# HeadphoneAmplifierUsingLM386.net
KiCad netlist of a schematic drawn in EAGLE
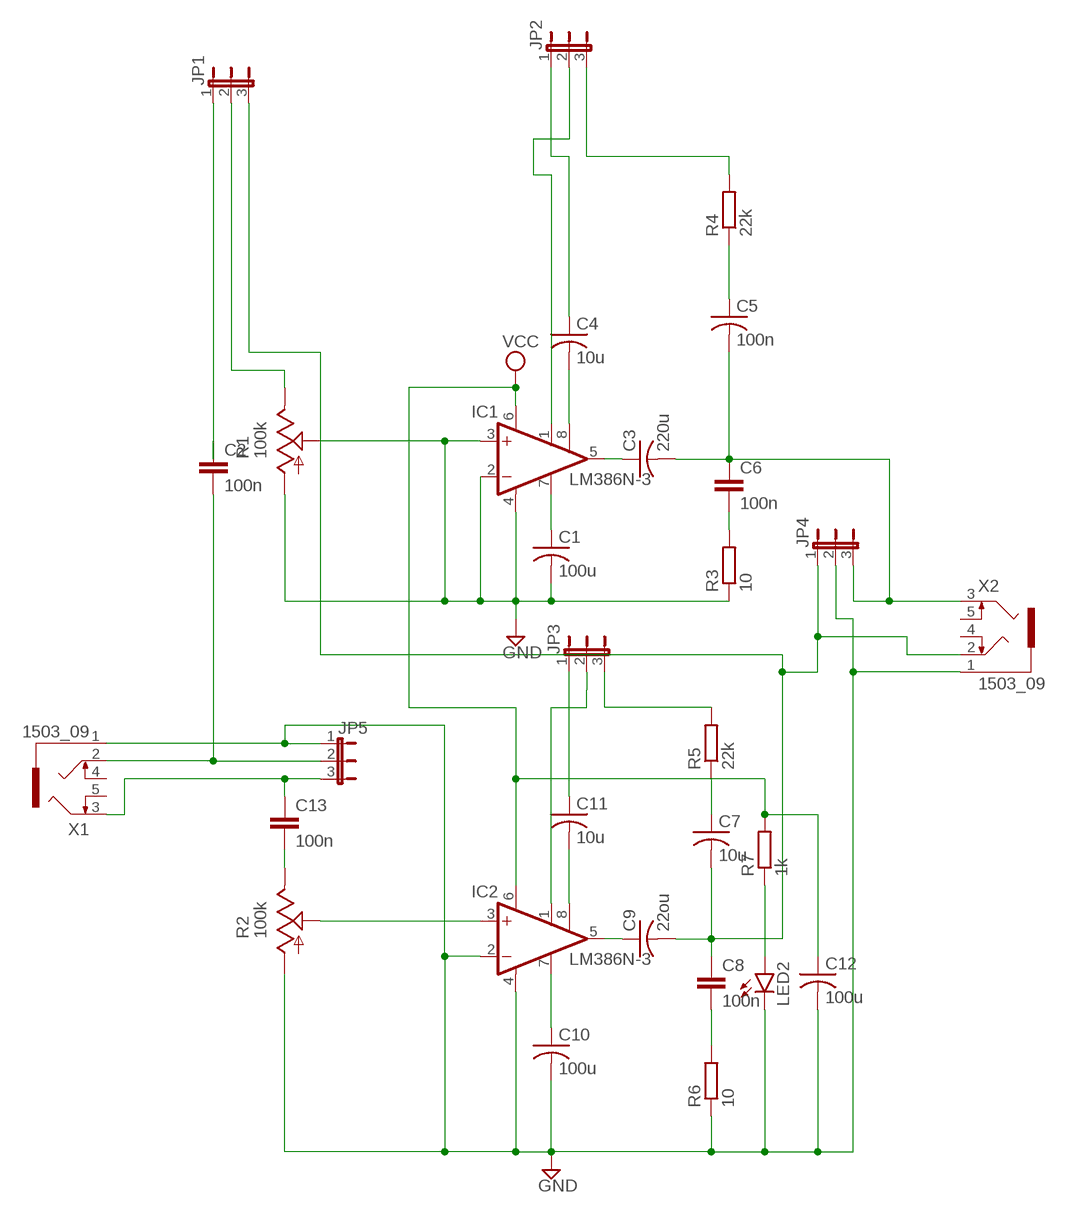
[diagram p0: schematic, sheet 1]

(export (version "E")
  (design (tool "Eeschema 10.0.6"))
  (components
    (comp (ref "C1")
      (value "100u")
      (footprint "eagle-import:C025-030X050")
      (libsource (lib "eagle-import") (part "C-US025-030X050"))
    )
    (comp (ref "C2")
      (value "100n")
      (footprint "eagle-import:C025-030X050")
      (libsource (lib "eagle-import") (part "C-EU025-030X050"))
    )
    (comp (ref "C3")
      (value "220u")
      (footprint "eagle-import:C025-030X050")
      (libsource (lib "eagle-import") (part "C-US025-030X050"))
    )
    (comp (ref "C4")
      (value "10u")
      (footprint "eagle-import:C025-030X050")
      (libsource (lib "eagle-import") (part "C-US025-030X050"))
    )
    (comp (ref "C5")
      (value "100n")
      (footprint "eagle-import:C025-030X050")
      (libsource (lib "eagle-import") (part "C-US025-030X050"))
    )
    (comp (ref "C6")
      (value "100n")
      (footprint "eagle-import:C025-030X050")
      (libsource (lib "eagle-import") (part "C-EU025-030X050"))
    )
    (comp (ref "C7")
      (value "10u")
      (footprint "eagle-import:C025-030X050")
      (libsource (lib "eagle-import") (part "C-US025-030X050"))
    )
    (comp (ref "C8")
      (value "100n")
      (footprint "eagle-import:C025-030X050")
      (libsource (lib "eagle-import") (part "C-EU025-030X050"))
    )
    (comp (ref "C9")
      (value "22ou")
      (footprint "eagle-import:C025-030X050")
      (libsource (lib "eagle-import") (part "C-US025-030X050"))
    )
    (comp (ref "C10")
      (value "100u")
      (footprint "eagle-import:C025-030X050")
      (libsource (lib "eagle-import") (part "C-US025-030X050"))
    )
    (comp (ref "C11")
      (value "10u")
      (footprint "eagle-import:C025-030X050")
      (libsource (lib "eagle-import") (part "C-US025-030X050"))
    )
    (comp (ref "C12")
      (value "100u")
      (footprint "eagle-import:C025-030X050")
      (libsource (lib "eagle-import") (part "C-US025-030X050"))
    )
    (comp (ref "C13")
      (value "100n")
      (footprint "eagle-import:C025-030X050")
      (libsource (lib "eagle-import") (part "C-EU025-030X050"))
    )
    (comp (ref "IC1")
      (value "LM386N-3")
      (footprint "eagle-import:DIL08")
      (libsource (lib "eagle-import") (part "LM386?-N3"))
    )
    (comp (ref "IC2")
      (value "LM386N-3")
      (footprint "eagle-import:DIL08")
      (libsource (lib "eagle-import") (part "LM386?-N3"))
    )
    (comp (ref "JP1")
      (value "JP2E")
      (footprint "eagle-import:JP2")
      (libsource (lib "eagle-import") (part "JP2E"))
    )
    (comp (ref "JP2")
      (value "JP2E")
      (footprint "eagle-import:JP2")
      (libsource (lib "eagle-import") (part "JP2E"))
    )
    (comp (ref "JP3")
      (value "JP2E")
      (footprint "eagle-import:JP2")
      (libsource (lib "eagle-import") (part "JP2E"))
    )
    (comp (ref "JP4")
      (value "JP2E")
      (footprint "eagle-import:JP2")
      (libsource (lib "eagle-import") (part "JP2E"))
    )
    (comp (ref "JP5")
      (value "JP2E")
      (footprint "eagle-import:JP2")
      (libsource (lib "eagle-import") (part "JP2E"))
    )
    (comp (ref "LED2")
      (value "LED3MM")
      (footprint "eagle-import:LED3MM")
      (libsource (lib "eagle-import") (part "LED3MM"))
    )
    (comp (ref "R1")
      (value "100k")
      (footprint "eagle-import:3223W")
      (libsource (lib "eagle-import") (part "TRIM_US-3223W"))
    )
    (comp (ref "R2")
      (value "100k")
      (footprint "eagle-import:3223W")
      (libsource (lib "eagle-import") (part "TRIM_US-3223W"))
    )
    (comp (ref "R3")
      (value "10")
      (footprint "eagle-import:0309_12")
      (libsource (lib "eagle-import") (part "R-EU_0309/12"))
    )
    (comp (ref "R4")
      (value "22k")
      (footprint "eagle-import:0309_12")
      (libsource (lib "eagle-import") (part "R-EU_0309/12"))
    )
    (comp (ref "R5")
      (value "22k")
      (footprint "eagle-import:0309_12")
      (libsource (lib "eagle-import") (part "R-EU_0309/12"))
    )
    (comp (ref "R6")
      (value "10")
      (footprint "eagle-import:0309_12")
      (libsource (lib "eagle-import") (part "R-EU_0309/12"))
    )
    (comp (ref "R7")
      (value "1k")
      (footprint "eagle-import:0309_12")
      (libsource (lib "eagle-import") (part "R-EU_0309/12"))
    )
    (comp (ref "X1")
      (value "1503_09")
      (footprint "eagle-import:1503_09")
      (libsource (lib "eagle-import") (part "1503_09"))
    )
    (comp (ref "X2")
      (value "1503_09")
      (footprint "eagle-import:1503_09")
      (libsource (lib "eagle-import") (part "1503_09"))
    )
  )
  (nets
    (net (code "1") (name "GND") (class "Default")
      (node (ref "C1") (pin "2") (pinfunction "2_2") (pintype "passive"))
      (node (ref "C10") (pin "2") (pinfunction "2_2") (pintype "passive"))
      (node (ref "C12") (pin "2") (pinfunction "2_2") (pintype "passive"))
      (node (ref "IC1") (pin "2") (pinfunction "-IN_2") (pintype "input"))
      (node (ref "IC1") (pin "3") (pinfunction "+IN_3") (pintype "input"))
      (node (ref "IC1") (pin "4") (pinfunction "GND_4") (pintype "power_in"))
      (node (ref "IC2") (pin "2") (pinfunction "-IN_2") (pintype "input"))
      (node (ref "IC2") (pin "4") (pinfunction "GND_4") (pintype "power_in"))
      (node (ref "JP4") (pin "2") (pinfunction "2_2") (pintype "passive"))
      (node (ref "JP5") (pin "1") (pinfunction "1_1") (pintype "passive"))
      (node (ref "LED2") (pin "K") (pinfunction "C_K") (pintype "passive"))
      (node (ref "R1") (pin "1") (pinfunction "A_1") (pintype "passive"))
      (node (ref "R1") (pin "2") (pinfunction "S_2") (pintype "passive"))
      (node (ref "R2") (pin "1") (pinfunction "A_1") (pintype "passive"))
      (node (ref "R3") (pin "1") (pinfunction "1_1") (pintype "passive"))
      (node (ref "R6") (pin "1") (pinfunction "1_1") (pintype "passive"))
      (node (ref "X1") (pin "1") (pinfunction "1_1") (pintype "passive"))
      (node (ref "X2") (pin "1") (pinfunction "1_1") (pintype "passive"))
    )
    (net (code "2") (name "Net-(C2-Pad1)") (class "Default")
      (node (ref "C2") (pin "1") (pinfunction "1_1") (pintype "passive"))
      (node (ref "JP1") (pin "1") (pinfunction "1_1") (pintype "passive"))
    )
    (net (code "3") (name "Net-(C2-Pad2)") (class "Default")
      (node (ref "C2") (pin "2") (pinfunction "2_2") (pintype "passive"))
      (node (ref "JP5") (pin "2") (pinfunction "2_2") (pintype "passive"))
      (node (ref "X1") (pin "2") (pinfunction "2_2") (pintype "passive"))
    )
    (net (code "4") (name "Net-(C3-Pad2)") (class "Default")
      (node (ref "C3") (pin "2") (pinfunction "2_2") (pintype "passive"))
      (node (ref "C5") (pin "2") (pinfunction "2_2") (pintype "passive"))
      (node (ref "C6") (pin "1") (pinfunction "1_1") (pintype "passive"))
      (node (ref "JP4") (pin "3") (pinfunction "3_3") (pintype "passive"))
      (node (ref "X2") (pin "3") (pinfunction "3_3") (pintype "passive"))
    )
    (net (code "5") (name "Net-(C4-Pad1)") (class "Default")
      (node (ref "C4") (pin "1") (pinfunction "1_1") (pintype "passive"))
      (node (ref "JP2") (pin "1") (pinfunction "1_1") (pintype "passive"))
    )
    (net (code "6") (name "Net-(C4-Pad2)") (class "Default")
      (node (ref "C4") (pin "2") (pinfunction "2_2") (pintype "passive"))
      (node (ref "IC1") (pin "8") (pinfunction "GAIN_8") (pintype "passive"))
    )
    (net (code "7") (name "Net-(C5-Pad1)") (class "Default")
      (node (ref "C5") (pin "1") (pinfunction "1_1") (pintype "passive"))
      (node (ref "R4") (pin "1") (pinfunction "1_1") (pintype "passive"))
    )
    (net (code "8") (name "Net-(C6-Pad2)") (class "Default")
      (node (ref "C6") (pin "2") (pinfunction "2_2") (pintype "passive"))
      (node (ref "R3") (pin "2") (pinfunction "2_2") (pintype "passive"))
    )
    (net (code "9") (name "Net-(C7-Pad1)") (class "Default")
      (node (ref "C7") (pin "1") (pinfunction "1_1") (pintype "passive"))
      (node (ref "R5") (pin "1") (pinfunction "1_1") (pintype "passive"))
    )
    (net (code "10") (name "Net-(C7-Pad2)") (class "Default")
      (node (ref "C7") (pin "2") (pinfunction "2_2") (pintype "passive"))
      (node (ref "C8") (pin "1") (pinfunction "1_1") (pintype "passive"))
      (node (ref "C9") (pin "2") (pinfunction "2_2") (pintype "passive"))
      (node (ref "JP1") (pin "3") (pinfunction "3_3") (pintype "passive"))
      (node (ref "JP4") (pin "1") (pinfunction "1_1") (pintype "passive"))
      (node (ref "X2") (pin "2") (pinfunction "2_2") (pintype "passive"))
    )
    (net (code "11") (name "Net-(C8-Pad2)") (class "Default")
      (node (ref "C8") (pin "2") (pinfunction "2_2") (pintype "passive"))
      (node (ref "R6") (pin "2") (pinfunction "2_2") (pintype "passive"))
    )
    (net (code "12") (name "Net-(C11-Pad1)") (class "Default")
      (node (ref "C11") (pin "1") (pinfunction "1_1") (pintype "passive"))
      (node (ref "JP3") (pin "1") (pinfunction "1_1") (pintype "passive"))
    )
    (net (code "13") (name "Net-(C11-Pad2)") (class "Default")
      (node (ref "C11") (pin "2") (pinfunction "2_2") (pintype "passive"))
      (node (ref "IC2") (pin "8") (pinfunction "GAIN_8") (pintype "passive"))
    )
    (net (code "14") (name "Net-(C13-Pad1)") (class "Default")
      (node (ref "C13") (pin "1") (pinfunction "1_1") (pintype "passive"))
      (node (ref "JP5") (pin "3") (pinfunction "3_3") (pintype "passive"))
      (node (ref "X1") (pin "3") (pinfunction "3_3") (pintype "passive"))
    )
    (net (code "15") (name "Net-(IC1-BYPASS)") (class "Default")
      (node (ref "C1") (pin "1") (pinfunction "1_1") (pintype "passive"))
      (node (ref "IC1") (pin "7") (pinfunction "BYPASS_7") (pintype "passive"))
    )
    (net (code "16") (name "Net-(IC1-GAIN-Pad1)") (class "Default")
      (node (ref "IC1") (pin "1") (pinfunction "GAIN_1") (pintype "passive"))
      (node (ref "JP2") (pin "2") (pinfunction "2_2") (pintype "passive"))
    )
    (net (code "17") (name "Net-(IC1-OUT)") (class "Default")
      (node (ref "C3") (pin "1") (pinfunction "1_1") (pintype "passive"))
      (node (ref "IC1") (pin "5") (pinfunction "OUT_5") (pintype "output"))
    )
    (net (code "18") (name "Net-(IC2-+IN)") (class "Default")
      (node (ref "IC2") (pin "3") (pinfunction "+IN_3") (pintype "input"))
      (node (ref "R2") (pin "2") (pinfunction "S_2") (pintype "passive"))
    )
    (net (code "19") (name "Net-(IC2-BYPASS)") (class "Default")
      (node (ref "C10") (pin "1") (pinfunction "1_1") (pintype "passive"))
      (node (ref "IC2") (pin "7") (pinfunction "BYPASS_7") (pintype "passive"))
    )
    (net (code "20") (name "Net-(IC2-GAIN-Pad1)") (class "Default")
      (node (ref "IC2") (pin "1") (pinfunction "GAIN_1") (pintype "passive"))
      (node (ref "JP3") (pin "2") (pinfunction "2_2") (pintype "passive"))
    )
    (net (code "21") (name "Net-(IC2-OUT)") (class "Default")
      (node (ref "C9") (pin "1") (pinfunction "1_1") (pintype "passive"))
      (node (ref "IC2") (pin "5") (pinfunction "OUT_5") (pintype "output"))
    )
    (net (code "22") (name "Net-(JP2-Pad3)") (class "Default")
      (node (ref "JP2") (pin "3") (pinfunction "3_3") (pintype "passive"))
      (node (ref "R4") (pin "2") (pinfunction "2_2") (pintype "passive"))
    )
    (net (code "23") (name "Net-(JP3-Pad3)") (class "Default")
      (node (ref "JP3") (pin "3") (pinfunction "3_3") (pintype "passive"))
      (node (ref "R5") (pin "2") (pinfunction "2_2") (pintype "passive"))
    )
    (net (code "24") (name "Net-(LED2-PadA)") (class "Default")
      (node (ref "LED2") (pin "A") (pinfunction "A_A") (pintype "passive"))
      (node (ref "R7") (pin "1") (pinfunction "1_1") (pintype "passive"))
    )
    (net (code "25") (name "Net-(R1-E)") (class "Default")
      (node (ref "JP1") (pin "2") (pinfunction "2_2") (pintype "passive"))
      (node (ref "R1") (pin "3") (pinfunction "E_3") (pintype "passive"))
    )
    (net (code "26") (name "Net-(R2-E)") (class "Default")
      (node (ref "C13") (pin "2") (pinfunction "2_2") (pintype "passive"))
      (node (ref "R2") (pin "3") (pinfunction "E_3") (pintype "passive"))
    )
    (net (code "27") (name "VCC") (class "Default")
      (node (ref "C12") (pin "1") (pinfunction "1_1") (pintype "passive"))
      (node (ref "IC1") (pin "6") (pinfunction "VS_6") (pintype "power_in"))
      (node (ref "IC2") (pin "6") (pinfunction "VS_6") (pintype "power_in"))
      (node (ref "R7") (pin "2") (pinfunction "2_2") (pintype "passive"))
    )
    (net (code "28") (name "unconnected-(X1-Pad4)") (class "Default")
      (node (ref "X1") (pin "4") (pinfunction "4_4") (pintype "passive"))
    )
    (net (code "29") (name "unconnected-(X1-Pad5)") (class "Default")
      (node (ref "X1") (pin "5") (pinfunction "5_5") (pintype "passive"))
    )
    (net (code "30") (name "unconnected-(X2-Pad4)") (class "Default")
      (node (ref "X2") (pin "4") (pinfunction "4_4") (pintype "passive"))
    )
    (net (code "31") (name "unconnected-(X2-Pad5)") (class "Default")
      (node (ref "X2") (pin "5") (pinfunction "5_5") (pintype "passive"))
    )
  )
)
